# ESP_DIN_V1_1.net
KiCad netlist of a schematic drawn in EAGLE
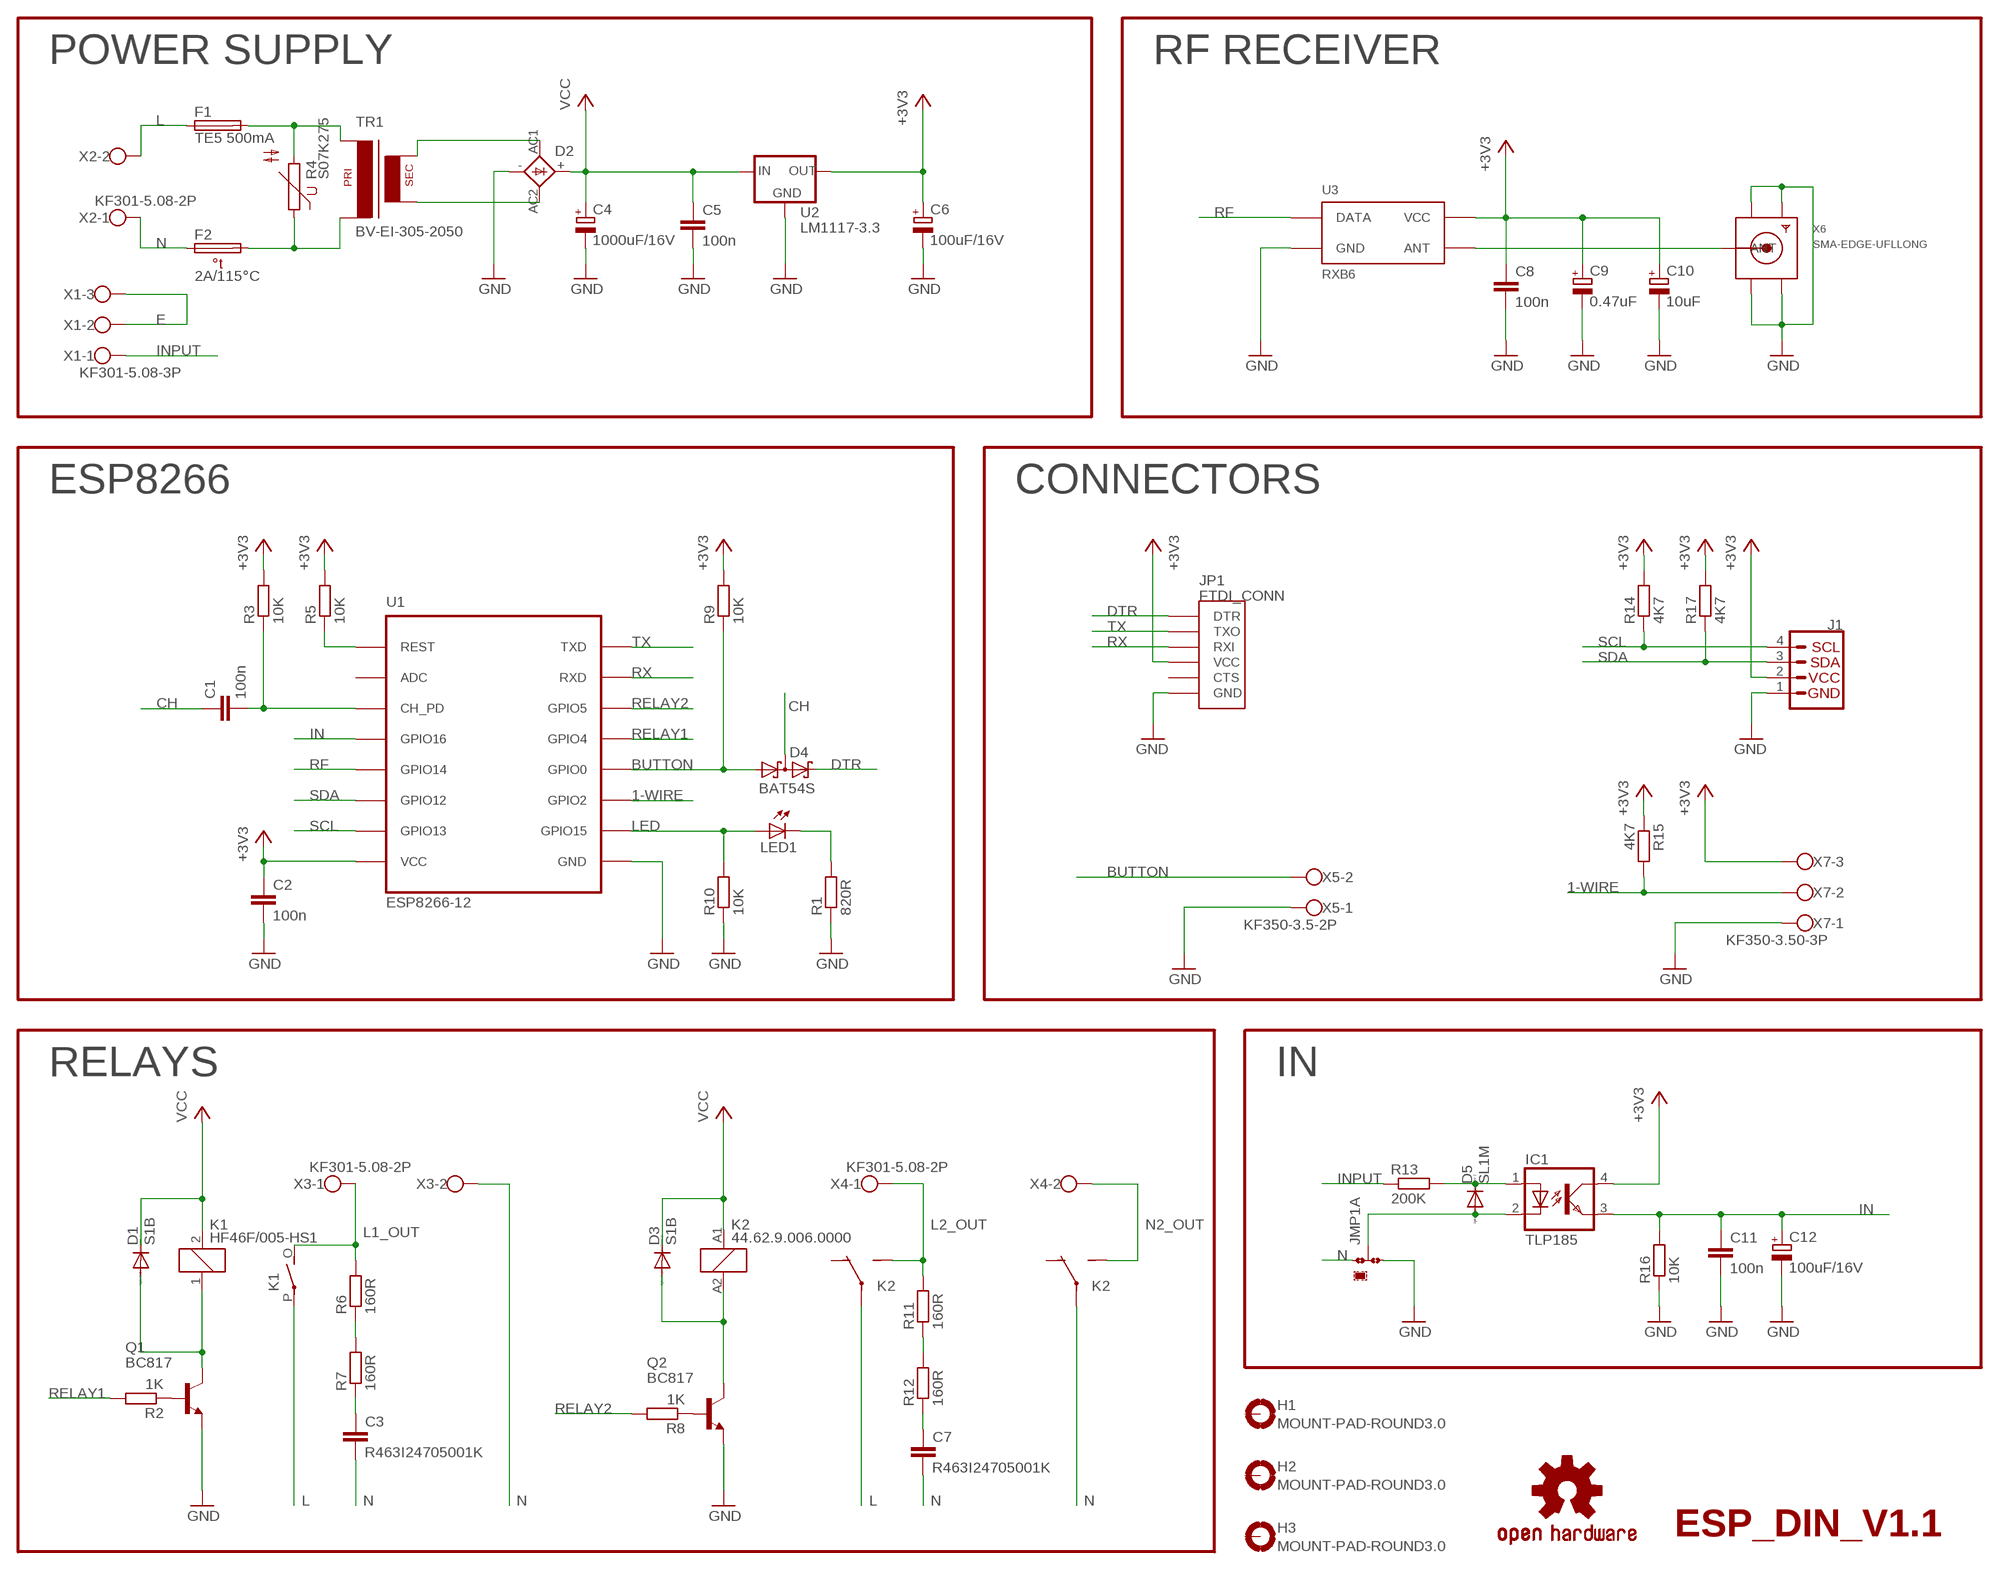
[diagram p0: schematic, sheet 1]

(export (version "E")
  (design (tool "Eeschema 10.0.6"))
  (components
    (comp (ref "C1")
      (value "100n")
      (footprint "eagle-import:C0805")
      (libsource (lib "eagle-import") (part "C-EUC0805"))
    )
    (comp (ref "C2")
      (value "100n")
      (footprint "eagle-import:C0805")
      (libsource (lib "eagle-import") (part "rcl_334_C-EUC0805"))
    )
    (comp (ref "C3")
      (value "R463I24705001K")
      (footprint "eagle-import:C150-084X183")
      (libsource (lib "eagle-import") (part "rcl_334_C-EU150-084X183"))
    )
    (comp (ref "C4")
      (value "1000uF/16V")
      (footprint "eagle-import:TT5D10")
      (libsource (lib "eagle-import") (part "CPOL-EUTT5D10"))
    )
    (comp (ref "C5")
      (value "100n")
      (footprint "eagle-import:C0805")
      (libsource (lib "eagle-import") (part "rcl_334_C-EUC0805"))
    )
    (comp (ref "C6")
      (value "100uF/16V")
      (footprint "eagle-import:E2-5")
      (libsource (lib "eagle-import") (part "CPOL-EUE2-5"))
    )
    (comp (ref "C7")
      (value "R463I24705001K")
      (footprint "eagle-import:C150-084X183")
      (libsource (lib "eagle-import") (part "rcl_334_C-EU150-084X183"))
    )
    (comp (ref "C8")
      (value "100n")
      (footprint "eagle-import:C0805")
      (libsource (lib "eagle-import") (part "C-EUC0805"))
    )
    (comp (ref "C9")
      (value "0.47uF")
      (footprint "eagle-import:SMC_A")
      (libsource (lib "eagle-import") (part "CPOL-EUSMCA"))
    )
    (comp (ref "C10")
      (value "10uF")
      (footprint "eagle-import:SMC_A")
      (libsource (lib "eagle-import") (part "CPOL-EUSMCA"))
    )
    (comp (ref "C11")
      (value "100n")
      (footprint "eagle-import:C0805")
      (libsource (lib "eagle-import") (part "rcl_334_C-EUC0805"))
    )
    (comp (ref "C12")
      (value "100uF/16V")
      (footprint "eagle-import:E2-5")
      (libsource (lib "eagle-import") (part "CPOL-EUE2-5"))
    )
    (comp (ref "D1")
      (value "S1B")
      (footprint "eagle-import:DO214AC")
      (libsource (lib "eagle-import") (part "S?1B"))
    )
    (comp (ref "D2")
      (value "KBP307")
      (footprint "eagle-import:KBP307")
      (libsource (lib "eagle-import") (part "KBP307"))
    )
    (comp (ref "D3")
      (value "S1B")
      (footprint "eagle-import:DO214AC")
      (libsource (lib "eagle-import") (part "S?1B"))
    )
    (comp (ref "D4")
      (value "BAT54S")
      (footprint "eagle-import:SOT23")
      (libsource (lib "eagle-import") (part "BAT54S"))
    )
    (comp (ref "D5")
      (value "SL1M")
      (footprint "eagle-import:SOD123")
      (libsource (lib "eagle-import") (part "SL1M"))
    )
    (comp (ref "F1")
      (value "TE5 500mA")
      (footprint "eagle-import:TE5")
      (libsource (lib "eagle-import") (part "TE5"))
    )
    (comp (ref "F2")
      (value "2A/115°C")
      (footprint "eagle-import:THERMAL_6.35")
      (libsource (lib "eagle-import") (part "THERMAL_CUTOFF"))
    )
    (comp (ref "H1")
      (value "MOUNT-PAD-ROUND3.0")
      (footprint "eagle-import:3,0-PAD")
      (libsource (lib "eagle-import") (part "MOUNT-PAD-ROUND3.0"))
    )
    (comp (ref "H2")
      (value "MOUNT-PAD-ROUND3.0")
      (footprint "eagle-import:3,0-PAD")
      (libsource (lib "eagle-import") (part "MOUNT-PAD-ROUND3.0"))
    )
    (comp (ref "H3")
      (value "MOUNT-PAD-ROUND3.0")
      (footprint "eagle-import:3,0-PAD")
      (libsource (lib "eagle-import") (part "MOUNT-PAD-ROUND3.0"))
    )
    (comp (ref "IC1")
      (value "TLP185")
      (footprint "eagle-import:SOP04")
      (libsource (lib "eagle-import") (part "TLP185"))
    )
    (comp (ref "J1")
      (value "I2C_STANDARD_NO_SILK")
      (footprint "eagle-import:1X04_NO_SILK")
      (libsource (lib "eagle-import") (part "I2C_STANDARD_NO_SILK"))
    )
    (comp (ref "JMP1")
      (value "JUMPER-0R-2010-A")
      (footprint "eagle-import:JUMPER-0R-2010-A")
      (libsource (lib "eagle-import") (part "JUMPER-0R-?-A2010"))
    )
    (comp (ref "JP1")
      (value "FTDI_CONN")
      (footprint "eagle-import:FTDI")
      (libsource (lib "eagle-import") (part "FTDI_CONN"))
    )
    (comp (ref "K1")
      (value "HF46F/005-HS1")
      (footprint "eagle-import:HF46F")
      (libsource (lib "eagle-import") (part "HF46F-G/-HS1006"))
    )
    (comp (ref "K2")
      (value "44.62.9.006.0000")
      (footprint "eagle-import:44.52")
      (libsource (lib "eagle-import") (part "44.62.9..0000006"))
    )
    (comp (ref "LED1")
      (value "LED3MM")
      (footprint "eagle-import:LED3MM")
      (libsource (lib "eagle-import") (part "LED3MM"))
    )
    (comp (ref "LOGO1")
      (value "OSHW-LOGOM-COPPER")
      (footprint "eagle-import:OSHW-LOGO-M_COPPER")
      (libsource (lib "eagle-import") (part "OSHW-LOGOM-COPPER"))
    )
    (comp (ref "Q1")
      (value "BC817")
      (footprint "eagle-import:SOT23-BEC")
      (libsource (lib "eagle-import") (part "BC817SMD-40"))
    )
    (comp (ref "Q2")
      (value "BC817")
      (footprint "eagle-import:SOT23-BEC")
      (libsource (lib "eagle-import") (part "BC817SMD-40"))
    )
    (comp (ref "R1")
      (value "820R")
      (footprint "eagle-import:R0805")
      (libsource (lib "eagle-import") (part "R-EU_R0805"))
    )
    (comp (ref "R2")
      (value "1K")
      (footprint "eagle-import:R0805")
      (libsource (lib "eagle-import") (part "R-EU_R0805"))
    )
    (comp (ref "R3")
      (value "10K")
      (footprint "eagle-import:R0805")
      (libsource (lib "eagle-import") (part "R-EU_R0805"))
    )
    (comp (ref "R4")
      (value "S07K275")
      (footprint "eagle-import:S07K250")
      (libsource (lib "eagle-import") (part "S07K250"))
    )
    (comp (ref "R5")
      (value "10K")
      (footprint "eagle-import:R0805")
      (libsource (lib "eagle-import") (part "R-EU_R0805"))
    )
    (comp (ref "R6")
      (value "160R")
      (footprint "eagle-import:R2010")
      (libsource (lib "eagle-import") (part "R-EU_R2010"))
    )
    (comp (ref "R7")
      (value "160R")
      (footprint "eagle-import:R2010")
      (libsource (lib "eagle-import") (part "R-EU_R2010"))
    )
    (comp (ref "R8")
      (value "1K")
      (footprint "eagle-import:R0805")
      (libsource (lib "eagle-import") (part "R-EU_R0805"))
    )
    (comp (ref "R9")
      (value "10K")
      (footprint "eagle-import:R0805")
      (libsource (lib "eagle-import") (part "R-EU_R0805"))
    )
    (comp (ref "R10")
      (value "10K")
      (footprint "eagle-import:R0805")
      (libsource (lib "eagle-import") (part "R-EU_R0805"))
    )
    (comp (ref "R11")
      (value "160R")
      (footprint "eagle-import:R2010")
      (libsource (lib "eagle-import") (part "R-EU_R2010"))
    )
    (comp (ref "R12")
      (value "160R")
      (footprint "eagle-import:R2010")
      (libsource (lib "eagle-import") (part "R-EU_R2010"))
    )
    (comp (ref "R13")
      (value "200K")
      (footprint "eagle-import:R2010")
      (libsource (lib "eagle-import") (part "R-EU_R2010"))
    )
    (comp (ref "R14")
      (value "4K7")
      (footprint "eagle-import:R0805")
      (libsource (lib "eagle-import") (part "R-EU_R0805"))
    )
    (comp (ref "R15")
      (value "4K7")
      (footprint "eagle-import:R0805")
      (libsource (lib "eagle-import") (part "R-EU_R0805"))
    )
    (comp (ref "R16")
      (value "10K")
      (footprint "eagle-import:R0805")
      (libsource (lib "eagle-import") (part "R-EU_R0805"))
    )
    (comp (ref "R17")
      (value "4K7")
      (footprint "eagle-import:R0805")
      (libsource (lib "eagle-import") (part "R-EU_R0805"))
    )
    (comp (ref "TR1")
      (value "BV-EI-305-2050")
      (footprint "eagle-import:EI30-1")
      (fields (field (name "VOLTAGE") "6"))
      (libsource (lib "eagle-import") (part "BV-EI-?305-2050"))
    )
    (comp (ref "U1")
      (value "ESP8266-12")
      (footprint "eagle-import:ESP-12")
      (libsource (lib "eagle-import") (part "ESP8266-12"))
    )
    (comp (ref "U2")
      (value "LM1117-3.3")
      (footprint "eagle-import:SOT223")
      (libsource (lib "eagle-import") (part "LM1117-3.3"))
    )
    (comp (ref "U3")
      (value "RXB6")
      (footprint "eagle-import:RXB6")
      (libsource (lib "eagle-import") (part "RXB6"))
    )
    (comp (ref "X1")
      (value "KF301-5.08-3P")
      (footprint "eagle-import:KF301-5.08-3P")
      (libsource (lib "eagle-import") (part "KF301-?-3P5.08"))
    )
    (comp (ref "X2")
      (value "KF301-5.08-2P")
      (footprint "eagle-import:KF301-5.08-2P")
      (libsource (lib "eagle-import") (part "KF301-?-2P5.08"))
    )
    (comp (ref "X3")
      (value "KF301-5.08-2P")
      (footprint "eagle-import:KF301-5.08-2P")
      (libsource (lib "eagle-import") (part "KF301-?-2P5.08"))
    )
    (comp (ref "X4")
      (value "KF301-5.08-2P")
      (footprint "eagle-import:KF301-5.08-2P")
      (libsource (lib "eagle-import") (part "KF301-?-2P5.08"))
    )
    (comp (ref "X5")
      (value "KF350-3.5-2P")
      (footprint "eagle-import:KF350-3.50-2P")
      (libsource (lib "eagle-import") (part "KF350-3.5-2P"))
    )
    (comp (ref "X6")
      (value "SMA-EDGE-UFLLONG")
      (footprint "eagle-import:SMA_EDGE_UFL_W")
      (libsource (lib "eagle-import") (part "SMA-EDGE-UFLLONG"))
    )
    (comp (ref "X7")
      (value "KF350-3.50-3P")
      (footprint "eagle-import:KF350-3.50-3P")
      (libsource (lib "eagle-import") (part "KF350-3.50-3P"))
    )
  )
  (nets
    (net (code "1") (name "+3V3") (class "Default")
      (node (ref "C10") (pin "+") (pinfunction "+_+") (pintype "passive"))
      (node (ref "C2") (pin "1") (pinfunction "1_1") (pintype "passive"))
      (node (ref "C6") (pin "+") (pinfunction "+_+") (pintype "passive"))
      (node (ref "C8") (pin "1") (pinfunction "1_1") (pintype "passive"))
      (node (ref "C9") (pin "+") (pinfunction "+_+") (pintype "passive"))
      (node (ref "IC1") (pin "4") (pinfunction "COL_4") (pintype "passive"))
      (node (ref "J1") (pin "2") (pinfunction "2_2") (pintype "power_in"))
      (node (ref "JP1") (pin "P$4") (pinfunction "VCC_P$4") (pintype "bidirectional"))
      (node (ref "R14") (pin "2") (pinfunction "2_2") (pintype "passive"))
      (node (ref "R15") (pin "1") (pinfunction "1_1") (pintype "passive"))
      (node (ref "R17") (pin "2") (pinfunction "2_2") (pintype "passive"))
      (node (ref "R3") (pin "2") (pinfunction "2_2") (pintype "passive"))
      (node (ref "R5") (pin "2") (pinfunction "2_2") (pintype "passive"))
      (node (ref "R9") (pin "2") (pinfunction "2_2") (pintype "passive"))
      (node (ref "U1") (pin "VCC") (pinfunction "VCC_VCC") (pintype "power_in"))
      (node (ref "U2") (pin "2") (pinfunction "OUT_2") (pintype "output"))
      (node (ref "U2") (pin "4") (pinfunction "OUT_4") (pintype "output"))
      (node (ref "U3") (pin "VCC") (pinfunction "VCC_VCC") (pintype "power_in"))
      (node (ref "U3") (pin "VCC@1") (pinfunction "VCC_VCC@1") (pintype "power_in"))
      (node (ref "X7") (pin "3") (pinfunction "KL_3") (pintype "passive"))
    )
    (net (code "2") (name "/1-WIRE") (class "Default")
      (node (ref "R15") (pin "2") (pinfunction "2_2") (pintype "passive"))
      (node (ref "U1") (pin "GPIO2") (pinfunction "GPIO2_GPIO2") (pintype "bidirectional"))
      (node (ref "X7") (pin "2") (pinfunction "KL_2") (pintype "passive"))
    )
    (net (code "3") (name "/BUTTON") (class "Default")
      (node (ref "D4") (pin "1") (pinfunction "A1_1") (pintype "passive"))
      (node (ref "R9") (pin "1") (pinfunction "1_1") (pintype "passive"))
      (node (ref "U1") (pin "GPIO0") (pinfunction "GPIO0_GPIO0") (pintype "bidirectional"))
      (node (ref "X5") (pin "2") (pinfunction "KL_2") (pintype "passive"))
    )
    (net (code "4") (name "/CH") (class "Default")
      (node (ref "C1") (pin "1") (pinfunction "1_1") (pintype "passive"))
      (node (ref "D4") (pin "3") (pinfunction "C1A2_3") (pintype "passive"))
    )
    (net (code "5") (name "/DTR") (class "Default")
      (node (ref "D4") (pin "2") (pinfunction "C2_2") (pintype "passive"))
      (node (ref "JP1") (pin "P$1") (pinfunction "DTR_P$1") (pintype "bidirectional"))
    )
    (net (code "6") (name "/E") (class "Default")
      (node (ref "X1") (pin "2") (pinfunction "KL_2") (pintype "passive"))
      (node (ref "X1") (pin "3") (pinfunction "KL_3") (pintype "passive"))
    )
    (net (code "7") (name "/IN") (class "Default")
      (node (ref "C11") (pin "1") (pinfunction "1_1") (pintype "passive"))
      (node (ref "C12") (pin "+") (pinfunction "+_+") (pintype "passive"))
      (node (ref "IC1") (pin "3") (pinfunction "EMIT_3") (pintype "passive"))
      (node (ref "R16") (pin "2") (pinfunction "2_2") (pintype "passive"))
      (node (ref "U1") (pin "GPIO16") (pinfunction "GPIO16_GPIO16") (pintype "bidirectional"))
    )
    (net (code "8") (name "/INPUT") (class "Default")
      (node (ref "R13") (pin "1") (pinfunction "1_1") (pintype "passive"))
      (node (ref "X1") (pin "1") (pinfunction "KL_1") (pintype "passive"))
    )
    (net (code "9") (name "/L") (class "Default")
      (node (ref "F1") (pin "1") (pinfunction "1_1") (pintype "passive"))
      (node (ref "K1") (pin "P") (pinfunction "P_P") (pintype "passive"))
      (node (ref "K2") (pin "11") (pinfunction "P_11") (pintype "passive"))
      (node (ref "X2") (pin "2") (pinfunction "KL_2") (pintype "passive"))
    )
    (net (code "10") (name "/L1_OUT") (class "Default")
      (node (ref "K1") (pin "O") (pinfunction "NO_O") (pintype "passive"))
      (node (ref "R6") (pin "2") (pinfunction "2_2") (pintype "passive"))
      (node (ref "X3") (pin "1") (pinfunction "KL_1") (pintype "passive"))
    )
    (net (code "11") (name "/L2_OUT") (class "Default")
      (node (ref "K2") (pin "14") (pinfunction "NO_14") (pintype "passive"))
      (node (ref "R11") (pin "2") (pinfunction "2_2") (pintype "passive"))
      (node (ref "X4") (pin "1") (pinfunction "KL_1") (pintype "passive"))
    )
    (net (code "12") (name "/LED") (class "Default")
      (node (ref "LED1") (pin "A") (pinfunction "A_A") (pintype "passive"))
      (node (ref "R10") (pin "2") (pinfunction "2_2") (pintype "passive"))
      (node (ref "U1") (pin "GPIO15") (pinfunction "GPIO15_GPIO15") (pintype "bidirectional"))
    )
    (net (code "13") (name "/N") (class "Default")
      (node (ref "C3") (pin "2") (pinfunction "2_2") (pintype "passive"))
      (node (ref "C7") (pin "2") (pinfunction "2_2") (pintype "passive"))
      (node (ref "F2") (pin "1") (pinfunction "1_1") (pintype "passive"))
      (node (ref "JMP1") (pin "1") (pinfunction "1_1") (pintype "passive"))
      (node (ref "K2") (pin "21") (pinfunction "P_21") (pintype "passive"))
      (node (ref "X2") (pin "1") (pinfunction "KL_1") (pintype "passive"))
      (node (ref "X3") (pin "2") (pinfunction "KL_2") (pintype "passive"))
    )
    (net (code "14") (name "/N2_OUT") (class "Default")
      (node (ref "K2") (pin "24") (pinfunction "NO_24") (pintype "passive"))
      (node (ref "X4") (pin "2") (pinfunction "KL_2") (pintype "passive"))
    )
    (net (code "15") (name "/RELAY1") (class "Default")
      (node (ref "R2") (pin "2") (pinfunction "2_2") (pintype "passive"))
      (node (ref "U1") (pin "GPIO5") (pinfunction "GPIO4_GPIO5") (pintype "bidirectional"))
    )
    (net (code "16") (name "/RELAY2") (class "Default")
      (node (ref "R8") (pin "2") (pinfunction "2_2") (pintype "passive"))
      (node (ref "U1") (pin "GPIO4") (pinfunction "GPIO5_GPIO4") (pintype "bidirectional"))
    )
    (net (code "17") (name "/RF") (class "Default")
      (node (ref "U1") (pin "GPIO14") (pinfunction "GPIO14_GPIO14") (pintype "bidirectional"))
      (node (ref "U3") (pin "DATA") (pinfunction "DATA_DATA") (pintype "output"))
    )
    (net (code "18") (name "/RX") (class "Default")
      (node (ref "JP1") (pin "P$3") (pinfunction "RXI_P$3") (pintype "bidirectional"))
      (node (ref "U1") (pin "RXD") (pinfunction "RXD_RXD") (pintype "bidirectional"))
    )
    (net (code "19") (name "/SCL") (class "Default")
      (node (ref "J1") (pin "4") (pinfunction "4_4") (pintype "passive"))
      (node (ref "R14") (pin "1") (pinfunction "1_1") (pintype "passive"))
      (node (ref "U1") (pin "GPIO13") (pinfunction "GPIO13_GPIO13") (pintype "bidirectional"))
    )
    (net (code "20") (name "/SDA") (class "Default")
      (node (ref "J1") (pin "3") (pinfunction "3_3") (pintype "passive"))
      (node (ref "R17") (pin "1") (pinfunction "1_1") (pintype "passive"))
      (node (ref "U1") (pin "GPIO12") (pinfunction "GPIO12_GPIO12") (pintype "bidirectional"))
    )
    (net (code "21") (name "/TX") (class "Default")
      (node (ref "JP1") (pin "P$2") (pinfunction "TXO_P$2") (pintype "bidirectional"))
      (node (ref "U1") (pin "TXD") (pinfunction "TXD_TXD") (pintype "bidirectional"))
    )
    (net (code "22") (name "GND") (class "Default")
      (node (ref "C10") (pin "-") (pinfunction "-_-") (pintype "passive"))
      (node (ref "C11") (pin "2") (pinfunction "2_2") (pintype "passive"))
      (node (ref "C12") (pin "-") (pinfunction "-_-") (pintype "passive"))
      (node (ref "C2") (pin "2") (pinfunction "2_2") (pintype "passive"))
      (node (ref "C4") (pin "-") (pinfunction "-_-") (pintype "passive"))
      (node (ref "C5") (pin "2") (pinfunction "2_2") (pintype "passive"))
      (node (ref "C6") (pin "-") (pinfunction "-_-") (pintype "passive"))
      (node (ref "C8") (pin "2") (pinfunction "2_2") (pintype "passive"))
      (node (ref "C9") (pin "-") (pinfunction "-_-") (pintype "passive"))
      (node (ref "D2") (pin "-") (pinfunction "-_-") (pintype "passive"))
      (node (ref "J1") (pin "1") (pinfunction "1_1") (pintype "power_in"))
      (node (ref "JMP1") (pin "3") (pinfunction "3_3") (pintype "passive"))
      (node (ref "JP1") (pin "P$6") (pinfunction "GND_P$6") (pintype "bidirectional"))
      (node (ref "Q1") (pin "E") (pinfunction "E_E") (pintype "passive"))
      (node (ref "Q2") (pin "E") (pinfunction "E_E") (pintype "passive"))
      (node (ref "R1") (pin "1") (pinfunction "1_1") (pintype "passive"))
      (node (ref "R10") (pin "1") (pinfunction "1_1") (pintype "passive"))
      (node (ref "R16") (pin "1") (pinfunction "1_1") (pintype "passive"))
      (node (ref "U1") (pin "GND") (pinfunction "GND_GND") (pintype "power_in"))
      (node (ref "U2") (pin "1") (pinfunction "GND_1") (pintype "input"))
      (node (ref "U3") (pin "GND") (pinfunction "GND_GND") (pintype "power_in"))
      (node (ref "U3") (pin "GND@1") (pinfunction "GND_GND@1") (pintype "power_in"))
      (node (ref "U3") (pin "GND@2") (pinfunction "GND_GND@2") (pintype "power_in"))
      (node (ref "X5") (pin "1") (pinfunction "KL_1") (pintype "passive"))
      (node (ref "X6") (pin "GND@1") (pinfunction "GND1_GND@1") (pintype "power_in"))
      (node (ref "X6") (pin "GND@2") (pinfunction "GND2_GND@2") (pintype "power_in"))
      (node (ref "X6") (pin "GND@3") (pinfunction "GND3_GND@3") (pintype "power_in"))
      (node (ref "X6") (pin "GND@4") (pinfunction "GND4_GND@4") (pintype "power_in"))
      (node (ref "X7") (pin "1") (pinfunction "KL_1") (pintype "passive"))
    )
    (net (code "23") (name "Net-(C1-Pad2)") (class "Default")
      (node (ref "C1") (pin "2") (pinfunction "2_2") (pintype "passive"))
      (node (ref "R3") (pin "1") (pinfunction "1_1") (pintype "passive"))
      (node (ref "U1") (pin "CH_PD") (pinfunction "CH_PD_CH_PD") (pintype "power_in"))
    )
    (net (code "24") (name "Net-(C3-Pad1)") (class "Default")
      (node (ref "C3") (pin "1") (pinfunction "1_1") (pintype "passive"))
      (node (ref "R7") (pin "1") (pinfunction "1_1") (pintype "passive"))
    )
    (net (code "25") (name "Net-(C7-Pad1)") (class "Default")
      (node (ref "C7") (pin "1") (pinfunction "1_1") (pintype "passive"))
      (node (ref "R12") (pin "1") (pinfunction "1_1") (pintype "passive"))
    )
    (net (code "26") (name "Net-(D1-PadA)") (class "Default")
      (node (ref "D1") (pin "A") (pinfunction "A_A") (pintype "passive"))
      (node (ref "K1") (pin "1") (pinfunction "1_1") (pintype "passive"))
      (node (ref "Q1") (pin "C") (pinfunction "C_C") (pintype "passive"))
    )
    (net (code "27") (name "Net-(IC1-A)") (class "Default")
      (node (ref "D5") (pin "C") (pinfunction "C_C") (pintype "passive"))
      (node (ref "IC1") (pin "1") (pinfunction "A_1") (pintype "passive"))
      (node (ref "R13") (pin "2") (pinfunction "2_2") (pintype "passive"))
    )
    (net (code "28") (name "Net-(IC1-C)") (class "Default")
      (node (ref "D5") (pin "A") (pinfunction "A_A") (pintype "passive"))
      (node (ref "IC1") (pin "2") (pinfunction "C_2") (pintype "passive"))
      (node (ref "JMP1") (pin "2") (pinfunction "2_2") (pintype "passive"))
    )
    (net (code "29") (name "Net-(K2A-2)") (class "Default")
      (node (ref "D3") (pin "A") (pinfunction "A_A") (pintype "passive"))
      (node (ref "K2") (pin "A2") (pinfunction "2_A2") (pintype "passive"))
      (node (ref "Q2") (pin "C") (pinfunction "C_C") (pintype "passive"))
    )
    (net (code "30") (name "Net-(LED1-C)") (class "Default")
      (node (ref "LED1") (pin "K") (pinfunction "C_K") (pintype "passive"))
      (node (ref "R1") (pin "2") (pinfunction "2_2") (pintype "passive"))
    )
    (net (code "31") (name "Net-(Q1-PadB)") (class "Default")
      (node (ref "Q1") (pin "B") (pinfunction "B_B") (pintype "passive"))
      (node (ref "R2") (pin "1") (pinfunction "1_1") (pintype "passive"))
    )
    (net (code "32") (name "Net-(Q2-PadB)") (class "Default")
      (node (ref "Q2") (pin "B") (pinfunction "B_B") (pintype "passive"))
      (node (ref "R8") (pin "1") (pinfunction "1_1") (pintype "passive"))
    )
    (net (code "33") (name "Net-(R5-Pad1)") (class "Default")
      (node (ref "R5") (pin "1") (pinfunction "1_1") (pintype "passive"))
      (node (ref "U1") (pin "REST") (pinfunction "REST_REST") (pintype "bidirectional"))
    )
    (net (code "34") (name "Net-(R6-Pad1)") (class "Default")
      (node (ref "R6") (pin "1") (pinfunction "1_1") (pintype "passive"))
      (node (ref "R7") (pin "2") (pinfunction "2_2") (pintype "passive"))
    )
    (net (code "35") (name "Net-(R11-Pad1)") (class "Default")
      (node (ref "R11") (pin "1") (pinfunction "1_1") (pintype "passive"))
      (node (ref "R12") (pin "2") (pinfunction "2_2") (pintype "passive"))
    )
    (net (code "36") (name "Net-(TR1-P1)") (class "Default")
      (node (ref "F1") (pin "2") (pinfunction "2_2") (pintype "passive"))
      (node (ref "R4") (pin "2") (pinfunction "2_2") (pintype "passive"))
      (node (ref "TR1") (pin "1") (pinfunction "P1_1") (pintype "passive"))
    )
    (net (code "37") (name "Net-(TR1-P2)") (class "Default")
      (node (ref "F2") (pin "2") (pinfunction "2_2") (pintype "passive"))
      (node (ref "R4") (pin "1") (pinfunction "1_1") (pintype "passive"))
      (node (ref "TR1") (pin "5") (pinfunction "P2_5") (pintype "passive"))
    )
    (net (code "38") (name "Net-(TR1-S3)") (class "Default")
      (node (ref "D2") (pin "AC2") (pinfunction "AC2_AC2") (pintype "passive"))
      (node (ref "TR1") (pin "7") (pinfunction "S3_7") (pintype "passive"))
    )
    (net (code "39") (name "Net-(TR1-S4)") (class "Default")
      (node (ref "D2") (pin "AC1") (pinfunction "AC1_AC1") (pintype "passive"))
      (node (ref "TR1") (pin "9") (pinfunction "S4_9") (pintype "passive"))
    )
    (net (code "40") (name "Net-(X6-ANT)") (class "Default")
      (node (ref "U3") (pin "ANT") (pinfunction "ANT_ANT") (pintype "output"))
      (node (ref "X6") (pin "P") (pinfunction "ANT_P") (pintype "bidirectional"))
    )
    (net (code "41") (name "VCC") (class "Default")
      (node (ref "C4") (pin "+") (pinfunction "+_+") (pintype "passive"))
      (node (ref "C5") (pin "1") (pinfunction "1_1") (pintype "passive"))
      (node (ref "D1") (pin "C") (pinfunction "C_C") (pintype "passive"))
      (node (ref "D2") (pin "+") (pinfunction "+_+") (pintype "passive"))
      (node (ref "D3") (pin "C") (pinfunction "C_C") (pintype "passive"))
      (node (ref "K1") (pin "2") (pinfunction "2_2") (pintype "passive"))
      (node (ref "K2") (pin "A1") (pinfunction "1_A1") (pintype "passive"))
      (node (ref "U2") (pin "3") (pinfunction "IN_3") (pintype "input"))
    )
    (net (code "42") (name "unconnected-(H1-MOUNT-PadB3,0)") (class "Default")
      (node (ref "H1") (pin "B3,0") (pinfunction "MOUNT_B3,0") (pintype "passive"))
    )
    (net (code "43") (name "unconnected-(H2-MOUNT-PadB3,0)") (class "Default")
      (node (ref "H2") (pin "B3,0") (pinfunction "MOUNT_B3,0") (pintype "passive"))
    )
    (net (code "44") (name "unconnected-(H3-MOUNT-PadB3,0)") (class "Default")
      (node (ref "H3") (pin "B3,0") (pinfunction "MOUNT_B3,0") (pintype "passive"))
    )
    (net (code "45") (name "unconnected-(JP1-CTS-PadP$5)") (class "Default")
      (node (ref "JP1") (pin "P$5") (pinfunction "CTS_P$5") (pintype "bidirectional"))
    )
    (net (code "46") (name "unconnected-(K2B-NC-Pad12)") (class "Default")
      (node (ref "K2") (pin "12") (pinfunction "NC_12") (pintype "passive"))
    )
    (net (code "47") (name "unconnected-(K2C-NC-Pad22)") (class "Default")
      (node (ref "K2") (pin "22") (pinfunction "NC_22") (pintype "passive"))
    )
    (net (code "48") (name "unconnected-(U1-PadADC)") (class "Default")
      (node (ref "U1") (pin "ADC") (pinfunction "ADC_ADC") (pintype "bidirectional"))
    )
  )
)
